# 02_PWR_IN.net
KiCad netlist of a schematic drawn in Altium Designer
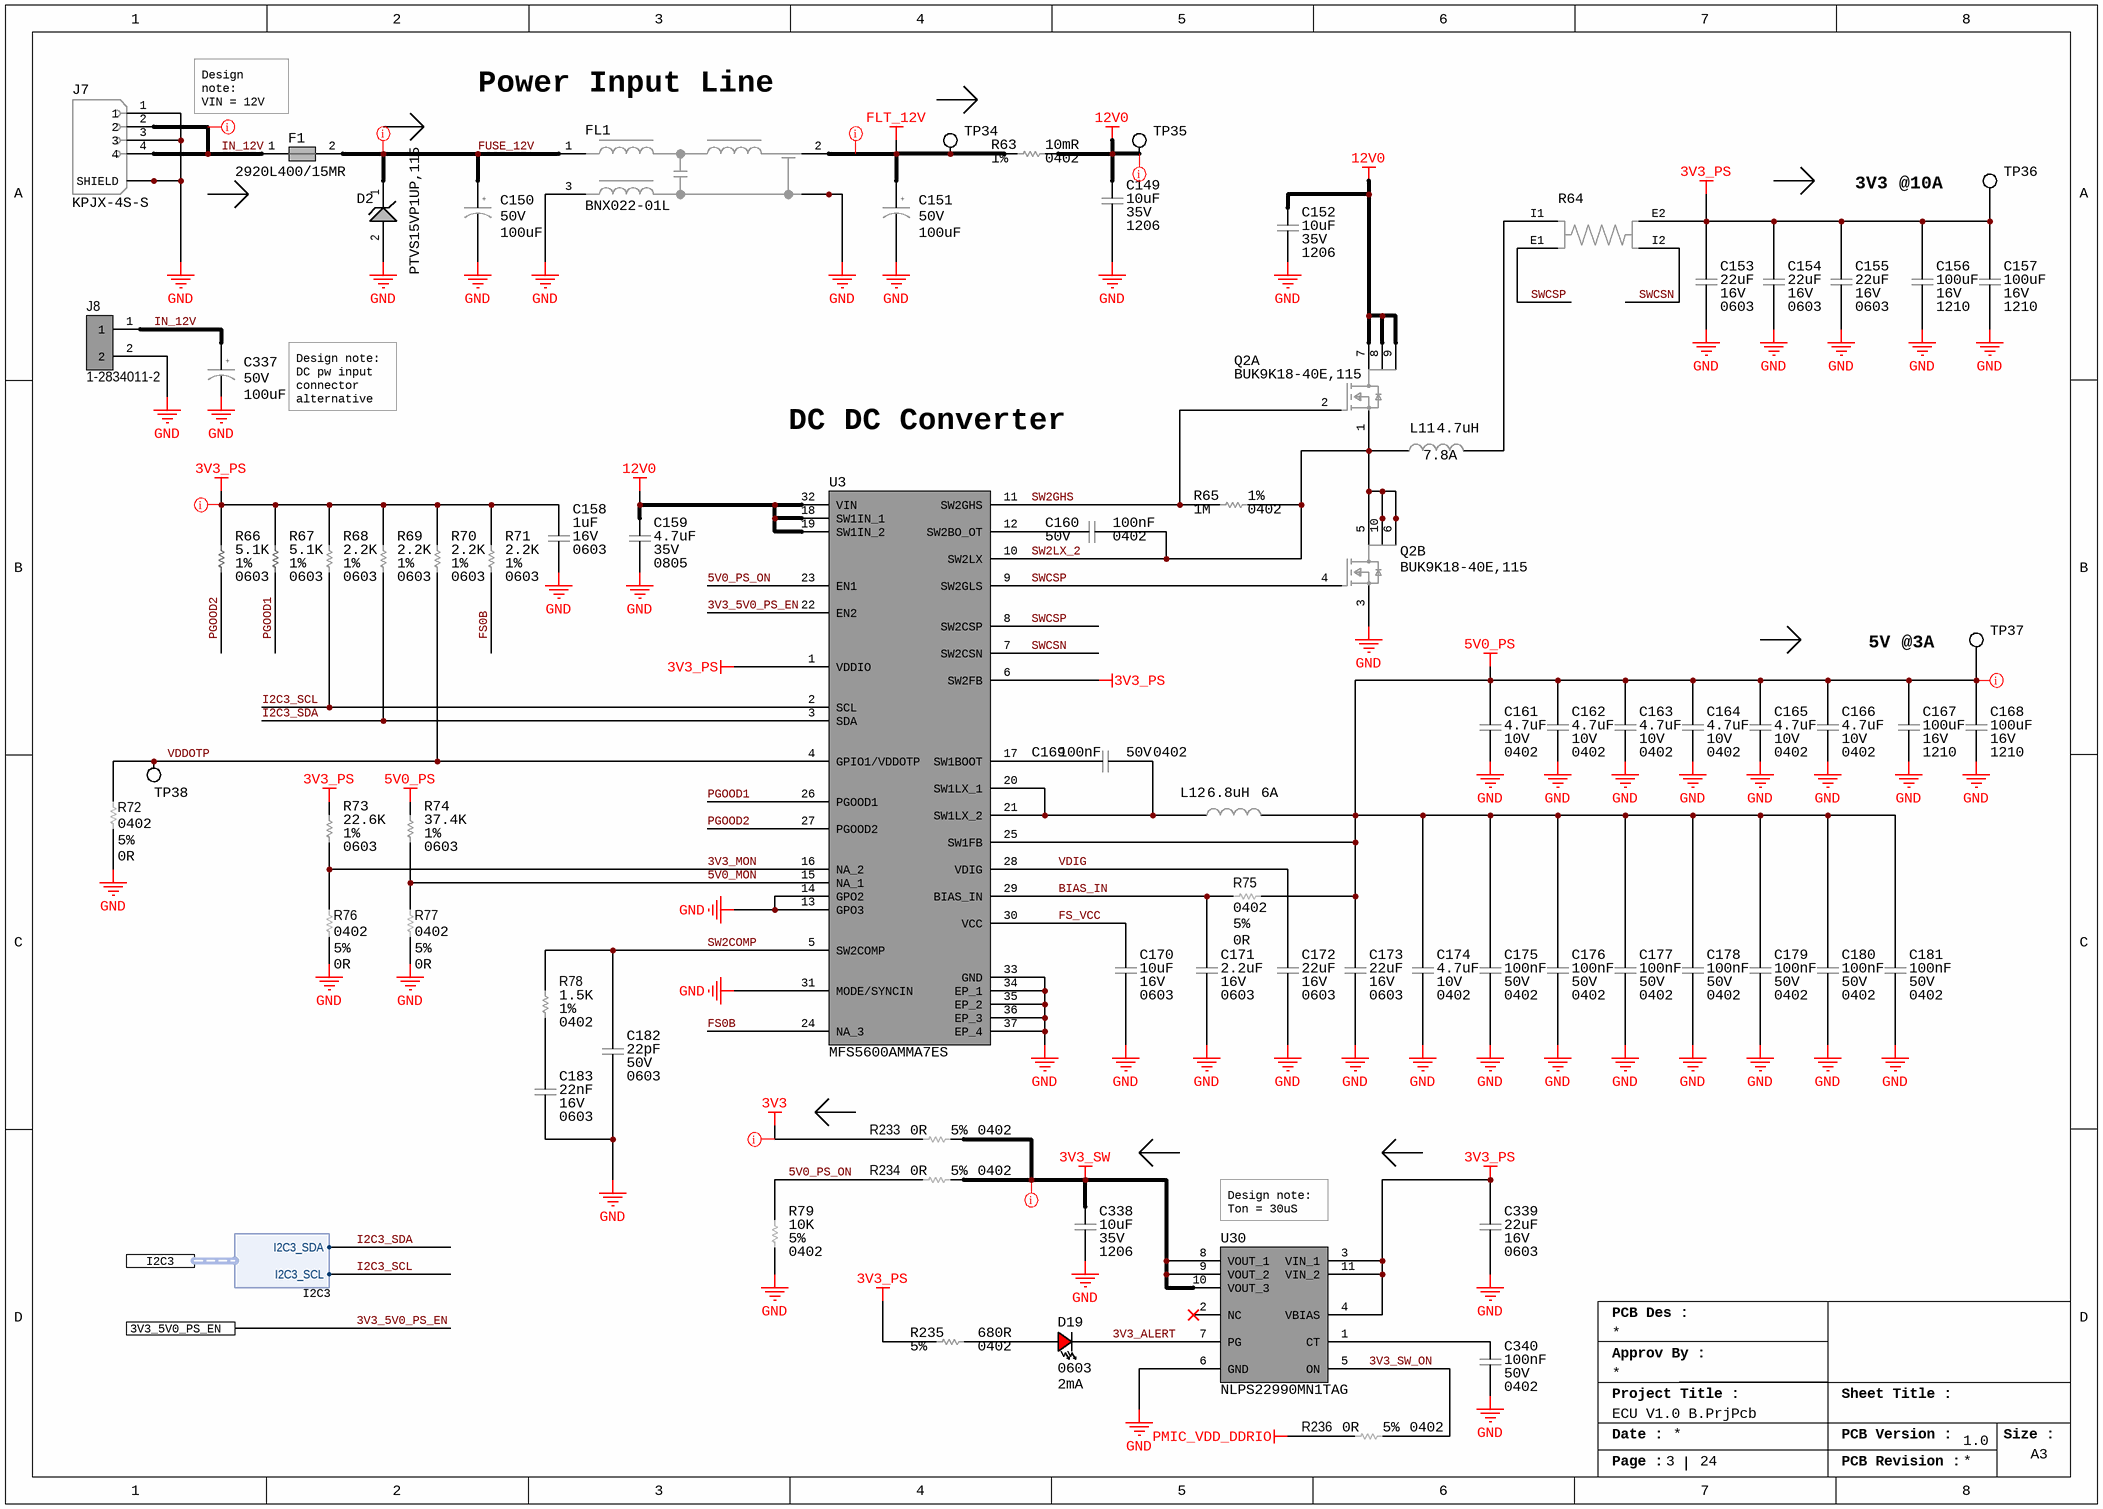
[diagram p0: 02_PWR IN.SchDoc]

(export (version "E")
  (design (tool "Eeschema 10.0.6"))
  (components
    (comp (ref "C149")
      (value "GRM319R6YA106KA12D")
      (footprint "CAP_1206_CAPC3216X16N")
      (description "1206 10 uF 35 V ±10 % Tolerance X5R SMT Multilayer Ceramic Capacitor")
      (fields
        (field (name "MANUFACTURER") "Murata")
        (field (name "TOLERANCE") "10%")
        (field (name "VOLTAGE RATING") "35V")
        (field (name "CAPACITANCE") "10uF")
        (field (name "CASE/PACKAGE") "1206")
      )
      (libsource (lib "Electronic Devices_LIB") (part "CAP_10uF_35V_X5R_1206"))
    )
    (comp (ref "C150")
      (value "UUD1H101MNL1GS")
      (footprint "CAP_POLA_UD(8X10)")
      (description "Radial Can - SMD ALUMINUM ELECTROLYTIC CAPACITOR UUD 50V 100muF ±20% 0.315Dia 8.00mm")
      (fields
        (field (name "MANUFACTURER") "Nichicon")
        (field (name "TOLERANCE") "20%")
        (field (name "VOLTAGE RATING (DC)") "50V")
        (field (name "CAPACITANCE") "100uF")
      )
      (libsource (lib "Electronic Devices_LIB") (part "CAP_100UF_50V_POL"))
    )
    (comp (ref "C151")
      (value "UUD1H101MNL1GS")
      (footprint "CAP_POLA_UD(8X10)")
      (description "Radial Can - SMD ALUMINUM ELECTROLYTIC CAPACITOR UUD 50V 100muF ±20% 0.315Dia 8.00mm")
      (fields
        (field (name "MANUFACTURER") "Nichicon")
        (field (name "TOLERANCE") "20%")
        (field (name "VOLTAGE RATING (DC)") "50V")
        (field (name "CAPACITANCE") "100uF")
      )
      (libsource (lib "Electronic Devices_LIB") (part "CAP_100UF_50V_POL"))
    )
    (comp (ref "C152")
      (value "GRM319R6YA106KA12D")
      (footprint "CAP_1206_CAPC3216X16N")
      (description "1206 10 uF 35 V ±10 % Tolerance X5R SMT Multilayer Ceramic Capacitor")
      (fields
        (field (name "MANUFACTURER") "Murata")
        (field (name "TOLERANCE") "10%")
        (field (name "VOLTAGE RATING") "35V")
        (field (name "CAPACITANCE") "10uF")
        (field (name "CASE/PACKAGE") "1206")
      )
      (libsource (lib "Electronic Devices_LIB") (part "CAP_10uF_35V_X5R_1206"))
    )
    (comp (ref "C153")
      (value "CL10A226MO7JZNC")
      (footprint "CAP_0603_CAPC1608X08N")
      (description "Cap Ceramic 22uF 16V X5R 20% Pad SMD 0603 85C T/R")
      (fields
        (field (name "MANUFACTURER") "Samsung")
        (field (name "TOLERANCE") "20%")
        (field (name "CAPACITANCE") "22uF")
        (field (name "VOLTAGE RATING") "16V")
        (field (name "CASE/PACKAGE") "0603")
      )
      (libsource (lib "Electronic Devices_LIB") (part "CAP_22UF_16V_X5R_0603"))
    )
    (comp (ref "C154")
      (value "CL10A226MO7JZNC")
      (footprint "CAP_0603_CAPC1608X08N")
      (description "Cap Ceramic 22uF 16V X5R 20% Pad SMD 0603 85C T/R")
      (fields
        (field (name "MANUFACTURER") "Samsung")
        (field (name "TOLERANCE") "20%")
        (field (name "CAPACITANCE") "22uF")
        (field (name "VOLTAGE RATING") "16V")
        (field (name "CASE/PACKAGE") "0603")
      )
      (libsource (lib "Electronic Devices_LIB") (part "CAP_22UF_16V_X5R_0603"))
    )
    (comp (ref "C155")
      (value "CL10A226MO7JZNC")
      (footprint "CAP_0603_CAPC1608X08N")
      (description "Cap Ceramic 22uF 16V X5R 20% Pad SMD 0603 85C T/R")
      (fields
        (field (name "MANUFACTURER") "Samsung")
        (field (name "TOLERANCE") "20%")
        (field (name "CAPACITANCE") "22uF")
        (field (name "VOLTAGE RATING") "16V")
        (field (name "CASE/PACKAGE") "0603")
      )
      (libsource (lib "Electronic Devices_LIB") (part "CAP_22UF_16V_X5R_0603"))
    )
    (comp (ref "C156")
      (value "EMK325ABJ107MM-T")
      (footprint "CAP_1210_CAPC3225X270N")
      (description "Multilayer Ceramic Capacitor, 100 uF, 16 V, ± 20%, X5R, 1210 [3225 Metric]")
      (fields
        (field (name "MANUFACTURER") "Taiyo Yuden")
        (field (name "TOLERANCE") "20%")
        (field (name "VOLTAGE RATING") "16V")
        (field (name "CAPACITANCE") "100uF")
        (field (name "CASE/PACKAGE") "1210")
      )
      (libsource (lib "Electronic Devices_LIB") (part "CAP_100UF_16V_X5R_1210"))
    )
    (comp (ref "C157")
      (value "EMK325ABJ107MM-T")
      (footprint "CAP_1210_CAPC3225X270N")
      (description "Multilayer Ceramic Capacitor, 100 uF, 16 V, ± 20%, X5R, 1210 [3225 Metric]")
      (fields
        (field (name "MANUFACTURER") "Taiyo Yuden")
        (field (name "TOLERANCE") "20%")
        (field (name "VOLTAGE RATING") "16V")
        (field (name "CAPACITANCE") "100uF")
        (field (name "CASE/PACKAGE") "1210")
      )
      (libsource (lib "Electronic Devices_LIB") (part "CAP_100UF_16V_X5R_1210"))
    )
    (comp (ref "C158")
      (value "CL10A105KO8NNNC")
      (footprint "CAP_0603_CAPC1608X08N")
      (description "CAP CER 1UF 16V X5R 0603")
      (fields
        (field (name "MANUFACTURER") "Samsung")
        (field (name "TOLERANCE") "10%")
        (field (name "VOLTAGE RATING") "16V")
        (field (name "CAPACITANCE") "1uF")
        (field (name "CASE/PACKAGE") "0603")
      )
      (libsource (lib "Electronic Devices_LIB") (part "CAP_1UF_16V_X5R_0603"))
    )
    (comp (ref "C159")
      (value "CL21A475KLCLQNC")
      (footprint "CAP_0805_CAPC2012X12N")
      (description "CL Series 0805 35 V 4.7 uF ±10% Tolerance X5R Multilayer Ceramic Chip Capacitor")
      (fields
        (field (name "MANUFACTURER") "Samsung")
        (field (name "TOLERANCE") "10%")
        (field (name "VOLTAGE RATING") "35V")
        (field (name "CAPACITANCE") "4.7uF")
        (field (name "CASE/PACKAGE") "0805")
      )
      (libsource (lib "Electronic Devices_LIB") (part "CAP_4.7uF_35V_X5R_0805"))
    )
    (comp (ref "C160")
      (value "GRM155R71H104KE14D")
      (footprint "CAP_0402_CAPC1005X05N")
      (description "Multilayer Ceramic Capacitor, 0.1 uF, 16 V, ± 10%, X7R, 0402 [1005 Metric]")
      (fields
        (field (name "MANUFACTURER") "Murata")
        (field (name "TOLERANCE") "10%")
        (field (name "VOLTAGE RATING") "50V")
        (field (name "CAPACITANCE") "100nF")
        (field (name "CASE/PACKAGE") "0402")
      )
      (libsource (lib "Electronic Devices_LIB") (part "CAP_100NF_50V_X7R_0402"))
    )
    (comp (ref "C161")
      (value "CL05A475KP5NRNC")
      (footprint "CAP_0402_CAPC1005X05N")
      (description "Multilayer Ceramic Capacitor, 4.7 uF, 10 V, ± 10%, X5R, 0402 [1005 Metric]")
      (fields
        (field (name "MANUFACTURER") "Samsung")
        (field (name "TOLERANCE") "10%")
        (field (name "CAPACITANCE") "4.7uF")
        (field (name "VOLTAGE RATING") "10V")
        (field (name "CASE/PACKAGE") "0402")
      )
      (libsource (lib "Electronic Devices_LIB") (part "CAP_4.7UF_10V_X5R_0402"))
    )
    (comp (ref "C162")
      (value "CL05A475KP5NRNC")
      (footprint "CAP_0402_CAPC1005X05N")
      (description "Multilayer Ceramic Capacitor, 4.7 uF, 10 V, ± 10%, X5R, 0402 [1005 Metric]")
      (fields
        (field (name "MANUFACTURER") "Samsung")
        (field (name "TOLERANCE") "10%")
        (field (name "CAPACITANCE") "4.7uF")
        (field (name "VOLTAGE RATING") "10V")
        (field (name "CASE/PACKAGE") "0402")
      )
      (libsource (lib "Electronic Devices_LIB") (part "CAP_4.7UF_10V_X5R_0402"))
    )
    (comp (ref "C163")
      (value "CL05A475KP5NRNC")
      (footprint "CAP_0402_CAPC1005X05N")
      (description "Multilayer Ceramic Capacitor, 4.7 uF, 10 V, ± 10%, X5R, 0402 [1005 Metric]")
      (fields
        (field (name "MANUFACTURER") "Samsung")
        (field (name "TOLERANCE") "10%")
        (field (name "CAPACITANCE") "4.7uF")
        (field (name "VOLTAGE RATING") "10V")
        (field (name "CASE/PACKAGE") "0402")
      )
      (libsource (lib "Electronic Devices_LIB") (part "CAP_4.7UF_10V_X5R_0402"))
    )
    (comp (ref "C164")
      (value "CL05A475KP5NRNC")
      (footprint "CAP_0402_CAPC1005X05N")
      (description "Multilayer Ceramic Capacitor, 4.7 uF, 10 V, ± 10%, X5R, 0402 [1005 Metric]")
      (fields
        (field (name "MANUFACTURER") "Samsung")
        (field (name "TOLERANCE") "10%")
        (field (name "CAPACITANCE") "4.7uF")
        (field (name "VOLTAGE RATING") "10V")
        (field (name "CASE/PACKAGE") "0402")
      )
      (libsource (lib "Electronic Devices_LIB") (part "CAP_4.7UF_10V_X5R_0402"))
    )
    (comp (ref "C165")
      (value "CL05A475KP5NRNC")
      (footprint "CAP_0402_CAPC1005X05N")
      (description "Multilayer Ceramic Capacitor, 4.7 uF, 10 V, ± 10%, X5R, 0402 [1005 Metric]")
      (fields
        (field (name "MANUFACTURER") "Samsung")
        (field (name "TOLERANCE") "10%")
        (field (name "CAPACITANCE") "4.7uF")
        (field (name "VOLTAGE RATING") "10V")
        (field (name "CASE/PACKAGE") "0402")
      )
      (libsource (lib "Electronic Devices_LIB") (part "CAP_4.7UF_10V_X5R_0402"))
    )
    (comp (ref "C166")
      (value "CL05A475KP5NRNC")
      (footprint "CAP_0402_CAPC1005X05N")
      (description "Multilayer Ceramic Capacitor, 4.7 uF, 10 V, ± 10%, X5R, 0402 [1005 Metric]")
      (fields
        (field (name "MANUFACTURER") "Samsung")
        (field (name "TOLERANCE") "10%")
        (field (name "CAPACITANCE") "4.7uF")
        (field (name "VOLTAGE RATING") "10V")
        (field (name "CASE/PACKAGE") "0402")
      )
      (libsource (lib "Electronic Devices_LIB") (part "CAP_4.7UF_10V_X5R_0402"))
    )
    (comp (ref "C167")
      (value "EMK325ABJ107MM-T")
      (footprint "CAP_1210_CAPC3225X270N")
      (description "Multilayer Ceramic Capacitor, 100 uF, 16 V, ± 20%, X5R, 1210 [3225 Metric]")
      (fields
        (field (name "MANUFACTURER") "Taiyo Yuden")
        (field (name "TOLERANCE") "20%")
        (field (name "VOLTAGE RATING") "16V")
        (field (name "CAPACITANCE") "100uF")
        (field (name "CASE/PACKAGE") "1210")
      )
      (libsource (lib "Electronic Devices_LIB") (part "CAP_100UF_16V_X5R_1210"))
    )
    (comp (ref "C168")
      (value "EMK325ABJ107MM-T")
      (footprint "CAP_1210_CAPC3225X270N")
      (description "Multilayer Ceramic Capacitor, 100 uF, 16 V, ± 20%, X5R, 1210 [3225 Metric]")
      (fields
        (field (name "MANUFACTURER") "Taiyo Yuden")
        (field (name "TOLERANCE") "20%")
        (field (name "VOLTAGE RATING") "16V")
        (field (name "CAPACITANCE") "100uF")
        (field (name "CASE/PACKAGE") "1210")
      )
      (libsource (lib "Electronic Devices_LIB") (part "CAP_100UF_16V_X5R_1210"))
    )
    (comp (ref "C169")
      (value "GRM155R71H104KE14D")
      (footprint "CAP_0402_CAPC1005X05N")
      (description "Multilayer Ceramic Capacitor, 0.1 uF, 16 V, ± 10%, X7R, 0402 [1005 Metric]")
      (fields
        (field (name "MANUFACTURER") "Murata")
        (field (name "TOLERANCE") "10%")
        (field (name "VOLTAGE RATING") "50V")
        (field (name "CAPACITANCE") "100nF")
        (field (name "CASE/PACKAGE") "0402")
      )
      (libsource (lib "Electronic Devices_LIB") (part "CAP_100NF_50V_X7R_0402"))
    )
    (comp (ref "C170")
      (value "GRM188R61C106MAALD")
      (footprint "CAP_0603_CAPC1608X08N")
      (description "0603 10 uF 16 V ±20% Tolerance X5R Multilayer Ceramic Chip Capacitor")
      (fields
        (field (name "MANUFACTURER") "Murata")
        (field (name "TOLERANCE") "20%")
        (field (name "VOLTAGE RATING") "16V")
        (field (name "CAPACITANCE") "10uF")
        (field (name "CASE/PACKAGE") "0603")
      )
      (libsource (lib "Electronic Devices_LIB") (part "CAP_10UF_16V_X5R_0603"))
    )
    (comp (ref "C171")
      (value "EMK107BB7225KA-T")
      (footprint "CAP_0603_CAPC1608X08N")
      (description "Multilayer Ceramic Capacitors (High dielectric type), 16V, 2.2 uF, ± 10 %, 0603, X7R, RoHS")
      (fields
        (field (name "MANUFACTURER") "Taiyo Yuden")
        (field (name "TOLERANCE") "10%")
        (field (name "CASE/PACKAGE") "0603")
        (field (name "CAPACITANCE") "2.2uF")
        (field (name "VOLTAGE RATING") "16V")
      )
      (libsource (lib "Electronic Devices_LIB") (part "CAP_2.2UF_16V_X7R_0603"))
    )
    (comp (ref "C172")
      (value "CL10A226MO7JZNC")
      (footprint "CAP_0603_CAPC1608X08N")
      (description "Cap Ceramic 22uF 16V X5R 20% Pad SMD 0603 85C T/R")
      (fields
        (field (name "MANUFACTURER") "Samsung")
        (field (name "TOLERANCE") "20%")
        (field (name "CAPACITANCE") "22uF")
        (field (name "VOLTAGE RATING") "16V")
        (field (name "CASE/PACKAGE") "0603")
      )
      (libsource (lib "Electronic Devices_LIB") (part "CAP_22UF_16V_X5R_0603"))
    )
    (comp (ref "C173")
      (value "CL10A226MO7JZNC")
      (footprint "CAP_0603_CAPC1608X08N")
      (description "Cap Ceramic 22uF 16V X5R 20% Pad SMD 0603 85C T/R")
      (fields
        (field (name "MANUFACTURER") "Samsung")
        (field (name "TOLERANCE") "20%")
        (field (name "CAPACITANCE") "22uF")
        (field (name "VOLTAGE RATING") "16V")
        (field (name "CASE/PACKAGE") "0603")
      )
      (libsource (lib "Electronic Devices_LIB") (part "CAP_22UF_16V_X5R_0603"))
    )
    (comp (ref "C174")
      (value "CL05A475KP5NRNC")
      (footprint "CAP_0402_CAPC1005X05N")
      (description "Multilayer Ceramic Capacitor, 4.7 uF, 10 V, ± 10%, X5R, 0402 [1005 Metric]")
      (fields
        (field (name "MANUFACTURER") "Samsung")
        (field (name "TOLERANCE") "10%")
        (field (name "CAPACITANCE") "4.7uF")
        (field (name "VOLTAGE RATING") "10V")
        (field (name "CASE/PACKAGE") "0402")
      )
      (libsource (lib "Electronic Devices_LIB") (part "CAP_4.7UF_10V_X5R_0402"))
    )
    (comp (ref "C175")
      (value "GRM155R71H104KE14D")
      (footprint "CAP_0402_CAPC1005X05N")
      (description "Multilayer Ceramic Capacitor, 0.1 uF, 16 V, ± 10%, X7R, 0402 [1005 Metric]")
      (fields
        (field (name "MANUFACTURER") "Murata")
        (field (name "TOLERANCE") "10%")
        (field (name "VOLTAGE RATING") "50V")
        (field (name "CAPACITANCE") "100nF")
        (field (name "CASE/PACKAGE") "0402")
      )
      (libsource (lib "Electronic Devices_LIB") (part "CAP_100NF_50V_X7R_0402"))
    )
    (comp (ref "C176")
      (value "GRM155R71H104KE14D")
      (footprint "CAP_0402_CAPC1005X05N")
      (description "Multilayer Ceramic Capacitor, 0.1 uF, 16 V, ± 10%, X7R, 0402 [1005 Metric]")
      (fields
        (field (name "MANUFACTURER") "Murata")
        (field (name "TOLERANCE") "10%")
        (field (name "VOLTAGE RATING") "50V")
        (field (name "CAPACITANCE") "100nF")
        (field (name "CASE/PACKAGE") "0402")
      )
      (libsource (lib "Electronic Devices_LIB") (part "CAP_100NF_50V_X7R_0402"))
    )
    (comp (ref "C177")
      (value "GRM155R71H104KE14D")
      (footprint "CAP_0402_CAPC1005X05N")
      (description "Multilayer Ceramic Capacitor, 0.1 uF, 16 V, ± 10%, X7R, 0402 [1005 Metric]")
      (fields
        (field (name "MANUFACTURER") "Murata")
        (field (name "TOLERANCE") "10%")
        (field (name "VOLTAGE RATING") "50V")
        (field (name "CAPACITANCE") "100nF")
        (field (name "CASE/PACKAGE") "0402")
      )
      (libsource (lib "Electronic Devices_LIB") (part "CAP_100NF_50V_X7R_0402"))
    )
    (comp (ref "C178")
      (value "GRM155R71H104KE14D")
      (footprint "CAP_0402_CAPC1005X05N")
      (description "Multilayer Ceramic Capacitor, 0.1 uF, 16 V, ± 10%, X7R, 0402 [1005 Metric]")
      (fields
        (field (name "MANUFACTURER") "Murata")
        (field (name "TOLERANCE") "10%")
        (field (name "VOLTAGE RATING") "50V")
        (field (name "CAPACITANCE") "100nF")
        (field (name "CASE/PACKAGE") "0402")
      )
      (libsource (lib "Electronic Devices_LIB") (part "CAP_100NF_50V_X7R_0402"))
    )
    (comp (ref "C179")
      (value "GRM155R71H104KE14D")
      (footprint "CAP_0402_CAPC1005X05N")
      (description "Multilayer Ceramic Capacitor, 0.1 uF, 16 V, ± 10%, X7R, 0402 [1005 Metric]")
      (fields
        (field (name "MANUFACTURER") "Murata")
        (field (name "TOLERANCE") "10%")
        (field (name "VOLTAGE RATING") "50V")
        (field (name "CAPACITANCE") "100nF")
        (field (name "CASE/PACKAGE") "0402")
      )
      (libsource (lib "Electronic Devices_LIB") (part "CAP_100NF_50V_X7R_0402"))
    )
    (comp (ref "C180")
      (value "GRM155R71H104KE14D")
      (footprint "CAP_0402_CAPC1005X05N")
      (description "Multilayer Ceramic Capacitor, 0.1 uF, 16 V, ± 10%, X7R, 0402 [1005 Metric]")
      (fields
        (field (name "MANUFACTURER") "Murata")
        (field (name "TOLERANCE") "10%")
        (field (name "VOLTAGE RATING") "50V")
        (field (name "CAPACITANCE") "100nF")
        (field (name "CASE/PACKAGE") "0402")
      )
      (libsource (lib "Electronic Devices_LIB") (part "CAP_100NF_50V_X7R_0402"))
    )
    (comp (ref "C181")
      (value "GRM155R71H104KE14D")
      (footprint "CAP_0402_CAPC1005X05N")
      (description "Multilayer Ceramic Capacitor, 0.1 uF, 16 V, ± 10%, X7R, 0402 [1005 Metric]")
      (fields
        (field (name "MANUFACTURER") "Murata")
        (field (name "TOLERANCE") "10%")
        (field (name "VOLTAGE RATING") "50V")
        (field (name "CAPACITANCE") "100nF")
        (field (name "CASE/PACKAGE") "0402")
      )
      (libsource (lib "Electronic Devices_LIB") (part "CAP_100NF_50V_X7R_0402"))
    )
    (comp (ref "C182")
      (value "C0603C220J5GACTU")
      (footprint "CAP_0603_CAPC1608X08N")
      (description "Multilayer Ceramic Capacitor, 22 pF, 50 V, ï¿½ 5%, C0G (NP0), 0603 [1608 Metric]")
      (fields
        (field (name "MANUFACTURER") "KEMET")
        (field (name "TOLERANCE") "5%")
        (field (name "VOLTAGE RATING (DC)") "50V")
        (field (name "CAPACITANCE") "22pF")
        (field (name "CASE/PACKAGE") "0603")
      )
      (libsource (lib "Electronic Devices_LIB") (part "CAP_22pF_50V_NP0_0603"))
    )
    (comp (ref "C183")
      (value "C0603C223K4RACTU")
      (footprint "CAP_0603_CAPC1608X08N")
      (description "Multilayer Ceramic Capacitor, 0.022 uF, 16 V, ± 10%, X7R, 0603 [1608 Metric]")
      (fields
        (field (name "MANUFACTURER") "KEMET")
        (field (name "TOLERANCE") "10%")
        (field (name "VOLTAGE RATING (DC)") "16V")
        (field (name "CAPACITANCE") "22nF")
        (field (name "CASE/PACKAGE") "0603")
      )
      (libsource (lib "Electronic Devices_LIB") (part "CAP_22nF_16V_X7R_0603"))
    )
    (comp (ref "C337")
      (value "UUD1H101MNL1GS")
      (footprint "CAP_POLA_UD(8X10)")
      (description "Radial Can - SMD ALUMINUM ELECTROLYTIC CAPACITOR UUD 50V 100muF ±20% 0.315Dia 8.00mm")
      (fields
        (field (name "MANUFACTURER") "Nichicon")
        (field (name "TOLERANCE") "20%")
        (field (name "VOLTAGE RATING (DC)") "50V")
        (field (name "CAPACITANCE") "100uF")
      )
      (libsource (lib "Electronic Devices_LIB") (part "CAP_100UF_50V_POL"))
    )
    (comp (ref "C338")
      (value "GRM319R6YA106KA12D")
      (footprint "CAP_1206_CAPC3216X16N")
      (description "1206 10 uF 35 V ±10 % Tolerance X5R SMT Multilayer Ceramic Capacitor")
      (fields
        (field (name "MANUFACTURER") "Murata")
        (field (name "TOLERANCE") "10%")
        (field (name "VOLTAGE RATING") "35V")
        (field (name "CAPACITANCE") "10uF")
        (field (name "CASE/PACKAGE") "1206")
      )
      (libsource (lib "Electronic Devices_LIB") (part "CAP_10uF_35V_X5R_1206"))
    )
    (comp (ref "C339")
      (value "CL10A226MO7JZNC")
      (footprint "CAP_0603_CAPC1608X08N")
      (description "Cap Ceramic 22uF 16V X5R 20% Pad SMD 0603 85C T/R")
      (fields
        (field (name "MANUFACTURER") "Samsung")
        (field (name "TOLERANCE") "20%")
        (field (name "CAPACITANCE") "22uF")
        (field (name "VOLTAGE RATING") "16V")
        (field (name "CASE/PACKAGE") "0603")
      )
      (libsource (lib "Electronic Devices_LIB") (part "CAP_22UF_16V_X5R_0603"))
    )
    (comp (ref "C340")
      (value "GRM155R71H104KE14D")
      (footprint "CAP_0402_CAPC1005X05N")
      (description "Multilayer Ceramic Capacitor, 0.1 uF, 16 V, ± 10%, X7R, 0402 [1005 Metric]")
      (fields
        (field (name "MANUFACTURER") "Murata")
        (field (name "TOLERANCE") "10%")
        (field (name "VOLTAGE RATING") "50V")
        (field (name "CAPACITANCE") "100nF")
        (field (name "CASE/PACKAGE") "0402")
      )
      (libsource (lib "Electronic Devices_LIB") (part "CAP_100NF_50V_X7R_0402"))
    )
    (comp (ref "D2")
      (value "PTVS15VP1UP,115")
      (footprint "PMEG3050EP115")
      (description "TVS DIODE 15VWM 24.4VC SOD128")
      (fields (field (name "MANUFACTURER") "Nexperia"))
      (libsource (lib "Electronic Devices_LIB") (part "DIO_TVS_24.4V_PTVS15VP1UP,115"))
    )
    (comp (ref "D19")
      (value "LTST-C193KRKT-2A")
      (footprint "LED_0603-RED-0.75mm")
      (description "Led Red Clear 0603 Smd")
      (fields
        (field (name "MANUFACTURER") "Vishay Lite-On")
        (field (name "CASE/PACKAGE") "0603")
        (field (name "TEST CURRENT") "2mA")
      )
      (libsource (lib "Electronic Devices_LIB") (part "LED_DIO_RED_2mA_0603_LTST-C193KRKT-2A"))
    )
    (comp (ref "F1")
      (value "2920L400/15MR")
      (footprint "2920L07560MR")
      (description "PTC Resettable Fuse 4A(hold) 8A(trip) 15VDC 40A 1.5W 4s 0.01Ohm SMD Solder Pad 2920 T/R")
      (fields (field (name "MANUFACTURER") "Littelfuse"))
      (libsource (lib "Electronic Devices_LIB") (part "FUSE_PTC_8A_2920L400/15MR"))
    )
    (comp (ref "FL1")
      (value "BNX022-01L")
      (footprint "FILTER_BNX022-01L")
      (description "EMI Filter 1MHz to 1000MHz 35dB 10A 50VDC Flat Style SMD Embossed T/R")
      (fields (field (name "MANUFACTURER") "Murata"))
      (libsource (lib "Electronic Devices_LIB") (part "FILTER_EMI_50VDC_10A_BNX022-01L"))
    )
    (comp (ref "J7")
      (value "KPJX-4S-S")
      (footprint "CONN_DC_KYCON_KPJX-4S-S")
      (description "Conn Power SKT 4 POS Solder ST Thru-Hole 4 Terminal 1 Port")
      (fields (field (name "MANUFACTURER") "Kycon"))
      (libsource (lib "Electronic Devices_LIB") (part "CONN_DC_JACK_PWR_KPJX-4S-S"))
    )
    (comp (ref "J8")
      (value "1-2834011-2")
      (footprint "CONN_TBLOCK_128340112")
      (description "2POS3.5MMTOPENTRYSCREWLESSC")
      (fields (field (name "MANUFACTURER") "TE Connectivity") (field (name "VOLTAGE") "300V"))
      (libsource (lib "Electronic Devices_LIB") (part "CONN_TBLOCK_2P_3.5mm_1-2834011-2"))
    )
    (comp (ref "L11")
      (value "SPM7054VT-4R7M-D")
      (footprint "SPM7054VT")
      (description "Inductor Power Shielded Wirewound 4.7uH 20% 100KHz Metal 7.8A 0.01826Ohm DCR Automotive T/R")
      (fields
        (field (name "MANUFACTURER") "TDK")
        (field (name "CURRENT RATING") "7.8A")
        (field (name "INDUCTANCE") "4.7uH")
      )
      (libsource (lib "Electronic Devices_LIB") (part "IND_4.7uH_7.8A_SPM7054VT-4R7M-D"))
    )
    (comp (ref "L12")
      (value "74437368068")
      (footprint "WE-LHMI_104048")
      (description "WE-LHMI; 6800 nH; Composite Iron Multilayer SMD Inductor; 1040 Case; .013GHz 6A")
      (fields
        (field (name "MANUFACTURER") "Wurth Electronics")
        (field (name "TOLERANCE") "20%")
        (field (name "MAX DC CURRENT") "6A")
        (field (name "INDUCTANCE") "6.8uH")
      )
      (libsource (lib "Electronic Devices_LIB") (part "IND_6.8uH_6A_74437368068"))
    )
    (comp (ref "Q2")
      (value "BUK9K18-40E,115")
      (footprint "BUK9K1840E115")
      (description "Transistor MOSFET Array Dual N -CH 40V 30A 8-Pin LFPAK-56D T/R")
      (fields (field (name "MANUFACTURER") "Nexperia"))
      (libsource (lib "Electronic Devices_LIB") (part "TRANS_FET_CH__N_40V_30A_BUK9K18-40E,115"))
    )
    (comp (ref "R63")
      (value "ERJ-2LWFR010X")
      (footprint "RES_0603_RESC1608X04N")
      (description "Res Current Sense Thick Film 0402 0.01 Ohm 1% 1/5W 0ppm/°C to 500ppm/°C Molded T/R")
      (fields
        (field (name "MANUFACTURER") "Panasonic")
        (field (name "TOLERANCE") "1%")
        (field (name "RESISTANCE") "10mR")
        (field (name "CASE/PACKAGE") "0402")
      )
      (libsource (lib "Electronic Devices_LIB") (part "RES_10mR_1%_0.05W_0402"))
    )
    (comp (ref "R64")
      (value "WSK2512R0100FEA")
      (footprint "RES_WSK2512R0100FEA")
      (description "Fixed Resistor, Metal Strip, 1W, 0.01ohm, 0.1V, 1% +/-Tol, 35ppm/Cel, Surface Mount, 2512")
      (fields (field (name "MANUFACTURER") "Vishay") (field (name "TOLERANCE") "1%"))
      (libsource (lib "Electronic Devices_LIB") (part "RES_10mR_1%_1W_2512"))
    )
    (comp (ref "R65")
      (value "CR0402-FX-1004GLF")
      (footprint "RES_0402_RESC1005X04N")
      (description "Res Thick Film 0402 1M Ohm 1% 1/16W ±100ppm/°C Molded SMD SMD Paper Tape on Plastic Reel")
      (fields
        (field (name "MANUFACTURER") "Bourns")
        (field (name "RESISTANCE") "1M")
        (field (name "TOLERANCE") "1%")
        (field (name "CASE/PACKAGE") "0402")
      )
      (libsource (lib "Electronic Devices_LIB") (part "RES_1M_1%_63mW_0402"))
    )
    (comp (ref "R66")
      (value "RC0603FR-075K1L")
      (footprint "RES_0603_RESC1608X04N")
      (description "SMD Chip Resistor, 5.1 kOhm, ± 1%, 100 mW, 0603 [1608 Metric], Thick Film, General Purpose")
      (fields
        (field (name "MANUFACTURER") "Yageo")
        (field (name "TOLERANCE") "1%")
        (field (name "RESISTANCE") "5.1K")
        (field (name "CASE/PACKAGE") "0603")
      )
      (libsource (lib "Electronic Devices_LIB") (part "RES_5.1K_1%_100mW_0603"))
    )
    (comp (ref "R67")
      (value "RC0603FR-075K1L")
      (footprint "RES_0603_RESC1608X04N")
      (description "SMD Chip Resistor, 5.1 kOhm, ± 1%, 100 mW, 0603 [1608 Metric], Thick Film, General Purpose")
      (fields
        (field (name "MANUFACTURER") "Yageo")
        (field (name "TOLERANCE") "1%")
        (field (name "RESISTANCE") "5.1K")
        (field (name "CASE/PACKAGE") "0603")
      )
      (libsource (lib "Electronic Devices_LIB") (part "RES_5.1K_1%_100mW_0603"))
    )
    (comp (ref "R68")
      (value "RC0603FR-072K2L")
      (footprint "RES_0603_RESC1608X04N")
      (description "SMD Chip Resistor, 2.2 Kohm, ½ 1%, 100 Mw, 0603 [1608 Metric], Thick Film, General Purpose")
      (fields
        (field (name "MANUFACTURER") "Yageo")
        (field (name "TOLERANCE") "1%")
        (field (name "RESISTANCE") "2.2K")
        (field (name "CASE/PACKAGE") "0603")
      )
      (libsource (lib "Electronic Devices_LIB") (part "RES_2.2K_1%_100mW_0603"))
    )
    (comp (ref "R69")
      (value "RC0603FR-072K2L")
      (footprint "RES_0603_RESC1608X04N")
      (description "SMD Chip Resistor, 2.2 Kohm, ½ 1%, 100 Mw, 0603 [1608 Metric], Thick Film, General Purpose")
      (fields
        (field (name "MANUFACTURER") "Yageo")
        (field (name "TOLERANCE") "1%")
        (field (name "RESISTANCE") "2.2K")
        (field (name "CASE/PACKAGE") "0603")
      )
      (libsource (lib "Electronic Devices_LIB") (part "RES_2.2K_1%_100mW_0603"))
    )
    (comp (ref "R70")
      (value "RC0603FR-072K2L")
      (footprint "RES_0603_RESC1608X04N")
      (description "SMD Chip Resistor, 2.2 Kohm, ½ 1%, 100 Mw, 0603 [1608 Metric], Thick Film, General Purpose")
      (fields
        (field (name "MANUFACTURER") "Yageo")
        (field (name "TOLERANCE") "1%")
        (field (name "RESISTANCE") "2.2K")
        (field (name "CASE/PACKAGE") "0603")
      )
      (libsource (lib "Electronic Devices_LIB") (part "RES_2.2K_1%_100mW_0603"))
    )
    (comp (ref "R71")
      (value "RC0603FR-072K2L")
      (footprint "RES_0603_RESC1608X04N")
      (description "SMD Chip Resistor, 2.2 Kohm, ½ 1%, 100 Mw, 0603 [1608 Metric], Thick Film, General Purpose")
      (fields
        (field (name "MANUFACTURER") "Yageo")
        (field (name "TOLERANCE") "1%")
        (field (name "RESISTANCE") "2.2K")
        (field (name "CASE/PACKAGE") "0603")
      )
      (libsource (lib "Electronic Devices_LIB") (part "RES_2.2K_1%_100mW_0603"))
    )
    (comp (ref "R72")
      (value "ERJ-2GE0R00X")
      (footprint "RES_0402_RESC1005X04N")
      (description "SMD Chip Resistor, Jumper, 0 ohm, 100 mW, 0402 [1005 Metric], Thick Film, General Purpose")
      (fields
        (field (name "MANUFACTURER") "Panasonic")
        (field (name "CASE CODE (IMPERIAL)") "0402")
        (field (name "TOLERANCE") "5%")
        (field (name "RESISTANCE") "0R")
      )
      (libsource (lib "Electronic Devices_LIB") (part "RES_0R_5%_100mW_0402"))
    )
    (comp (ref "R73")
      (value "AC0603FR-0722K6L")
      (footprint "RES_0603_RESC1608X04N")
      (description "Res Thick Film 0603 22.6K Ohm 1% 0.1W(1/10W) ±100ppm/C Pad SMD Automotive T/R")
      (fields
        (field (name "MANUFACTURER") "Yageo")
        (field (name "TOLERANCE") "1%")
        (field (name "RESISTANCE") "22.6K")
        (field (name "CASE/PACKAGE") "0603")
      )
      (libsource (lib "Electronic Devices_LIB") (part "RES_22.6K_1%_100mW_0603"))
    )
    (comp (ref "R74")
      (value "RC0603FR-0737K4L")
      (footprint "RES_0603_RESC1608X04N")
      (description "SMD Chip Resistor, 37.4 kOhm, ± 1%, 100 mW, 0603 [1608 Metric], Thick Film, General Purpose")
      (fields
        (field (name "MANUFACTURER") "Yageo")
        (field (name "TOLERANCE") "1%")
        (field (name "RESISTANCE") "37.4K")
        (field (name "CASE/PACKAGE") "0603")
      )
      (libsource (lib "Electronic Devices_LIB") (part "RES_37.4K_1%_100mW_0603"))
    )
    (comp (ref "R75")
      (value "ERJ-2GE0R00X")
      (footprint "RES_0402_RESC1005X04N")
      (description "SMD Chip Resistor, Jumper, 0 ohm, 100 mW, 0402 [1005 Metric], Thick Film, General Purpose")
      (fields
        (field (name "MANUFACTURER") "Panasonic")
        (field (name "CASE CODE (IMPERIAL)") "0402")
        (field (name "TOLERANCE") "5%")
        (field (name "RESISTANCE") "0R")
      )
      (libsource (lib "Electronic Devices_LIB") (part "RES_0R_5%_100mW_0402"))
    )
    (comp (ref "R76")
      (value "ERJ-2GE0R00X")
      (footprint "RES_0402_RESC1005X04N")
      (description "SMD Chip Resistor, Jumper, 0 ohm, 100 mW, 0402 [1005 Metric], Thick Film, General Purpose")
      (fields
        (field (name "MANUFACTURER") "Panasonic")
        (field (name "CASE CODE (IMPERIAL)") "0402")
        (field (name "TOLERANCE") "5%")
        (field (name "RESISTANCE") "0R")
      )
      (libsource (lib "Electronic Devices_LIB") (part "RES_0R_5%_100mW_0402"))
    )
    (comp (ref "R77")
      (value "ERJ-2GE0R00X")
      (footprint "RES_0402_RESC1005X04N")
      (description "SMD Chip Resistor, Jumper, 0 ohm, 100 mW, 0402 [1005 Metric], Thick Film, General Purpose")
      (fields
        (field (name "MANUFACTURER") "Panasonic")
        (field (name "CASE CODE (IMPERIAL)") "0402")
        (field (name "TOLERANCE") "5%")
        (field (name "RESISTANCE") "0R")
      )
      (libsource (lib "Electronic Devices_LIB") (part "RES_0R_5%_100mW_0402"))
    )
    (comp (ref "R78")
      (value "CR0402-FX-1501GLF")
      (footprint "RES_0402_RESC1005X04N")
      (description "Res Thick Film 0402 1.5K Ohm 1% 1/16W ±100ppm/°C Molded SMD SMD Paper Tape on Plastic Reel")
      (fields
        (field (name "MANUFACTURER") "Bourns")
        (field (name "RESISTANCE") "1.5K")
        (field (name "TOLERANCE") "1%")
        (field (name "CASE/PACKAGE") "0402")
      )
      (libsource (lib "Electronic Devices_LIB") (part "RES_1.5K_1%_63mW_0402"))
    )
    (comp (ref "R79")
      (value "ERJ-2GEJ103X")
      (footprint "RES_0402_RESC1005X04N")
      (description "Res Thick Film 0402 10K Ohm 5% 1/10W ±200ppm/°C Molded SMD Punched Carrier T/R")
      (fields
        (field (name "MANUFACTURER") "Panasonic")
        (field (name "TOLERANCE") "5%")
        (field (name "RESISTANCE") "10K")
        (field (name "CASE/PACKAGE") "0402")
      )
      (libsource (lib "Electronic Devices_LIB") (part "RES_10K_5%_100mW_0402"))
    )
    (comp (ref "R233")
      (value "ERJ-2GE0R00X")
      (footprint "RES_0402_RESC1005X04N")
      (description "SMD Chip Resistor, Jumper, 0 ohm, 100 mW, 0402 [1005 Metric], Thick Film, General Purpose")
      (fields
        (field (name "MANUFACTURER") "Panasonic")
        (field (name "CASE CODE (IMPERIAL)") "0402")
        (field (name "TOLERANCE") "5%")
        (field (name "RESISTANCE") "0R")
      )
      (libsource (lib "Electronic Devices_LIB") (part "RES_0R_5%_100mW_0402"))
    )
    (comp (ref "R234")
      (value "ERJ-2GE0R00X")
      (footprint "RES_0402_RESC1005X04N")
      (description "SMD Chip Resistor, Jumper, 0 ohm, 100 mW, 0402 [1005 Metric], Thick Film, General Purpose")
      (fields
        (field (name "MANUFACTURER") "Panasonic")
        (field (name "CASE CODE (IMPERIAL)") "0402")
        (field (name "TOLERANCE") "5%")
        (field (name "RESISTANCE") "0R")
      )
      (libsource (lib "Electronic Devices_LIB") (part "RES_0R_5%_100mW_0402"))
    )
    (comp (ref "R235")
      (value "ERJ-2GEJ681X")
      (footprint "RES_0402_RESC1005X04N")
      (description "SMD Chip Resistor, 680 Ohm, ± 5%, 100 mW, 0402 [1005 Metric], Thick Film, General Purpose")
      (fields
        (field (name "MANUFACTURER") "Panasonic")
        (field (name "TOLERANCE") "5%")
        (field (name "RESISTANCE") "680R")
        (field (name "CASE/PACKAGE") "0402")
      )
      (libsource (lib "Electronic Devices_LIB") (part "RES_680R_5%_100mW_0402"))
    )
    (comp (ref "R236")
      (value "ERJ-2GE0R00X")
      (footprint "RES_0402_RESC1005X04N")
      (description "SMD Chip Resistor, Jumper, 0 ohm, 100 mW, 0402 [1005 Metric], Thick Film, General Purpose")
      (fields
        (field (name "MANUFACTURER") "Panasonic")
        (field (name "CASE CODE (IMPERIAL)") "0402")
        (field (name "TOLERANCE") "5%")
        (field (name "RESISTANCE") "0R")
      )
      (libsource (lib "Electronic Devices_LIB") (part "RES_0R_5%_100mW_0402"))
    )
    (comp (ref "TP34")
      (value "NO COMPONENT")
      (footprint "TP_PAD_0.5MM_SMD_ROUND")
      (description "Test Point, SMD pad, round, 1.5mm, 1.6mm, 3mm diameter")
      (libsource (lib "Electronic Devices_LIB") (part "TP_PAD_SMD_SMALL"))
    )
    (comp (ref "TP35")
      (value "NO COMPONENT")
      (footprint "TP_PAD_0.5MM_SMD_ROUND")
      (description "Test Point, SMD pad, round, 1.5mm, 1.6mm, 3mm diameter")
      (libsource (lib "Electronic Devices_LIB") (part "TP_PAD_SMD_SMALL"))
    )
    (comp (ref "TP36")
      (value "NO COMPONENT")
      (footprint "TP_PAD_0.5MM_SMD_ROUND")
      (description "Test Point, SMD pad, round, 1.5mm, 1.6mm, 3mm diameter")
      (libsource (lib "Electronic Devices_LIB") (part "TP_PAD_SMD_SMALL"))
    )
    (comp (ref "TP37")
      (value "NO COMPONENT")
      (footprint "TP_PAD_0.5MM_SMD_ROUND")
      (description "Test Point, SMD pad, round, 1.5mm, 1.6mm, 3mm diameter")
      (libsource (lib "Electronic Devices_LIB") (part "TP_PAD_SMD_SMALL"))
    )
    (comp (ref "TP38")
      (value "NO COMPONENT")
      (footprint "TP_PAD_0.5MM_SMD_ROUND")
      (description "Test Point, SMD pad, round, 1.5mm, 1.6mm, 3mm diameter")
      (libsource (lib "Electronic Devices_LIB") (part "TP_PAD_SMD_SMALL"))
    )
    (comp (ref "U3")
      (value "MFS5600AMMA7ES")
      (footprint "MFS5600AMMA7ES")
      (description "Power Management, 36 V, 2 Step-Down DC-DC Converters, 2 Regulated Outputs, 32 Pins, HVQFN-EP")
      (fields (field (name "MANUFACTURER") "NXP Semiconductors"))
      (libsource (lib "Electronic Devices_LIB") (part "IC_REG_BUCK_MFS5600AMMA7ES"))
    )
    (comp (ref "U30")
      (value "NLPS22990MN1TAG")
      (footprint "SON50P200X300X80-11N")
      (description "5.5 V, 10 A, 3.9 mΩ On-Resistance Load Switch 5.5 V, 10 A, 3.9 mOhm On-Resistance")
      (fields (field (name "MANUFACTURER") "onsemi"))
      (libsource (lib "Electronic Devices_LIB") (part "IC_LOAD_SW_NLPS22990MN1TAG"))
    )
  )
  (nets
    (net (code "2") (name "/3V3_5V0_PS_EN") (class "Default")
      (node (ref "U3") (pin "22") (pinfunction "EN2_22") (pintype "passive"))
    )
    (net (code "3") (name "/3V3_ALERT") (class "Default")
      (node (ref "D19") (pin "1") (pinfunction "C_1") (pintype "passive"))
      (node (ref "U30") (pin "7") (pinfunction "PG_7") (pintype "passive"))
    )
    (net (code "4") (name "/3V3_MON") (class "Default")
      (node (ref "R73") (pin "1") (pinfunction "1_1") (pintype "passive"))
      (node (ref "R76") (pin "2") (pinfunction "2_2") (pintype "passive"))
      (node (ref "U3") (pin "16") (pinfunction "NA_2_16") (pintype "passive"))
    )
    (net (code "5") (name "/3V3_SW_ON") (class "Default")
      (node (ref "R236") (pin "1") (pinfunction "1_1") (pintype "passive"))
      (node (ref "U30") (pin "5") (pinfunction "ON_5") (pintype "passive"))
    )
    (net (code "6") (name "/5V0_MON") (class "Default")
      (node (ref "R74") (pin "1") (pinfunction "1_1") (pintype "passive"))
      (node (ref "R77") (pin "2") (pinfunction "2_2") (pintype "passive"))
      (node (ref "U3") (pin "15") (pinfunction "NA_1_15") (pintype "passive"))
    )
    (net (code "7") (name "/5V0_PS_ON") (class "Default")
      (node (ref "R234") (pin "2") (pinfunction "2_2") (pintype "passive"))
      (node (ref "R79") (pin "1") (pinfunction "1_1") (pintype "passive"))
      (node (ref "U3") (pin "23") (pinfunction "EN1_23") (pintype "passive"))
    )
    (net (code "8") (name "/BIAS_IN") (class "Default")
      (node (ref "C171") (pin "2") (pinfunction "2_2") (pintype "passive"))
      (node (ref "R75") (pin "2") (pinfunction "2_2") (pintype "passive"))
      (node (ref "U3") (pin "29") (pinfunction "BIAS_IN_29") (pintype "passive"))
    )
    (net (code "9") (name "/FS0B") (class "Default")
      (node (ref "R71") (pin "1") (pinfunction "1_1") (pintype "passive"))
      (node (ref "U3") (pin "24") (pinfunction "NA_3_24") (pintype "passive"))
    )
    (net (code "10") (name "/FS_VCC") (class "Default")
      (node (ref "C170") (pin "2") (pinfunction "2_2") (pintype "passive"))
      (node (ref "U3") (pin "30") (pinfunction "VCC_30") (pintype "passive"))
    )
    (net (code "11") (name "/FUSE_12V") (class "Default")
      (node (ref "C150") (pin "1") (pinfunction "1_1") (pintype "passive"))
      (node (ref "D2") (pin "1") (pinfunction "K_1") (pintype "passive"))
      (node (ref "F1") (pin "2") (pinfunction "2_2") (pintype "passive"))
      (node (ref "FL1") (pin "1") (pinfunction "B_1") (pintype "passive"))
    )
    (net (code "12") (name "/I2C3_SCL") (class "Default")
      (node (ref "R68") (pin "1") (pinfunction "1_1") (pintype "passive"))
      (node (ref "U3") (pin "2") (pinfunction "SCL_2") (pintype "passive"))
    )
    (net (code "13") (name "/I2C3_SDA") (class "Default")
      (node (ref "R69") (pin "1") (pinfunction "1_1") (pintype "passive"))
      (node (ref "U3") (pin "3") (pinfunction "SDA_3") (pintype "passive"))
    )
    (net (code "14") (name "/IN_12V") (class "Default")
      (node (ref "C337") (pin "1") (pinfunction "1_1") (pintype "passive"))
      (node (ref "F1") (pin "1") (pinfunction "1_1") (pintype "passive"))
      (node (ref "J7") (pin "2") (pinfunction "2_2") (pintype "passive"))
      (node (ref "J7") (pin "4") (pinfunction "4_4") (pintype "passive"))
      (node (ref "J8") (pin "1") (pinfunction "1_1") (pintype "passive"))
    )
    (net (code "15") (name "/PGOOD1") (class "Default")
      (node (ref "R67") (pin "1") (pinfunction "1_1") (pintype "passive"))
      (node (ref "U3") (pin "26") (pinfunction "PGOOD1_26") (pintype "passive"))
    )
    (net (code "16") (name "/PGOOD2") (class "Default")
      (node (ref "R66") (pin "1") (pinfunction "1_1") (pintype "passive"))
      (node (ref "U3") (pin "27") (pinfunction "PGOOD2_27") (pintype "passive"))
    )
    (net (code "17") (name "/SW2COMP") (class "Default")
      (node (ref "C182") (pin "2") (pinfunction "2_2") (pintype "passive"))
      (node (ref "R78") (pin "2") (pinfunction "2_2") (pintype "passive"))
      (node (ref "U3") (pin "5") (pinfunction "SW2COMP_5") (pintype "passive"))
    )
    (net (code "18") (name "/SW2GHS") (class "Default")
      (node (ref "Q2") (pin "2") (pinfunction "G1_2") (pintype "passive"))
      (node (ref "R65") (pin "1") (pinfunction "1_1") (pintype "passive"))
      (node (ref "U3") (pin "11") (pinfunction "SW2GHS_11") (pintype "passive"))
    )
    (net (code "19") (name "/SW2LX_2") (class "Default")
      (node (ref "C160") (pin "1") (pinfunction "1_1") (pintype "passive"))
      (node (ref "L11") (pin "1") (pinfunction "1_1") (pintype "passive"))
      (node (ref "Q2") (pin "1") (pinfunction "S1_1") (pintype "passive"))
      (node (ref "Q2") (pin "10") (pinfunction "D2_3_10") (pintype "passive"))
      (node (ref "Q2") (pin "5") (pinfunction "D2_1_5") (pintype "passive"))
      (node (ref "Q2") (pin "6") (pinfunction "D2_2_6") (pintype "passive"))
      (node (ref "R65") (pin "2") (pinfunction "2_2") (pintype "passive"))
      (node (ref "U3") (pin "10") (pinfunction "SW2LX_10") (pintype "passive"))
    )
    (net (code "20") (name "/SWCSN") (class "Default")
      (node (ref "R64") (pin "I2") (pinfunction "I2_I2") (pintype "passive"))
      (node (ref "U3") (pin "7") (pinfunction "SW2CSN_7") (pintype "passive"))
    )
    (net (code "21") (name "/SWCSP") (class "Default")
      (node (ref "Q2") (pin "4") (pinfunction "G2_4") (pintype "passive"))
      (node (ref "R64") (pin "E1") (pinfunction "E1_E1") (pintype "passive"))
      (node (ref "U3") (pin "8") (pinfunction "SW2CSP_8") (pintype "passive"))
      (node (ref "U3") (pin "9") (pinfunction "SW2GLS_9") (pintype "passive"))
    )
    (net (code "22") (name "/VDDOTP") (class "Default")
      (node (ref "R70") (pin "1") (pinfunction "1_1") (pintype "passive"))
      (node (ref "R72") (pin "2") (pinfunction "2_2") (pintype "passive"))
      (node (ref "TP38") (pin "1") (pinfunction "1_1") (pintype "passive"))
      (node (ref "U3") (pin "4") (pinfunction "GPIO1/VDDOTP_4") (pintype "passive"))
    )
    (net (code "23") (name "/VDIG") (class "Default")
      (node (ref "C172") (pin "2") (pinfunction "2_2") (pintype "passive"))
      (node (ref "U3") (pin "28") (pinfunction "VDIG_28") (pintype "passive"))
    )
    (net (code "25") (name "3V3") (class "Default")
      (node (ref "R233") (pin "2") (pinfunction "2_2") (pintype "passive"))
    )
    (net (code "26") (name "3V3_PS") (class "Default")
      (node (ref "C153") (pin "2") (pinfunction "2_2") (pintype "passive"))
      (node (ref "C154") (pin "2") (pinfunction "2_2") (pintype "passive"))
      (node (ref "C155") (pin "2") (pinfunction "2_2") (pintype "passive"))
      (node (ref "C156") (pin "2") (pinfunction "2_2") (pintype "passive"))
      (node (ref "C157") (pin "2") (pinfunction "2_2") (pintype "passive"))
      (node (ref "C158") (pin "2") (pinfunction "2_2") (pintype "passive"))
      (node (ref "C339") (pin "2") (pinfunction "2_2") (pintype "passive"))
      (node (ref "R235") (pin "1") (pinfunction "1_1") (pintype "passive"))
      (node (ref "R64") (pin "E2") (pinfunction "E2_E2") (pintype "passive"))
      (node (ref "R66") (pin "2") (pinfunction "2_2") (pintype "passive"))
      (node (ref "R67") (pin "2") (pinfunction "2_2") (pintype "passive"))
      (node (ref "R68") (pin "2") (pinfunction "2_2") (pintype "passive"))
      (node (ref "R69") (pin "2") (pinfunction "2_2") (pintype "passive"))
      (node (ref "R70") (pin "2") (pinfunction "2_2") (pintype "passive"))
      (node (ref "R71") (pin "2") (pinfunction "2_2") (pintype "passive"))
      (node (ref "R73") (pin "2") (pinfunction "2_2") (pintype "passive"))
      (node (ref "TP36") (pin "1") (pinfunction "1_1") (pintype "passive"))
      (node (ref "U3") (pin "1") (pinfunction "VDDIO_1") (pintype "passive"))
      (node (ref "U3") (pin "6") (pinfunction "SW2FB_6") (pintype "passive"))
      (node (ref "U30") (pin "11") (pinfunction "VIN_2_11") (pintype "passive"))
      (node (ref "U30") (pin "3") (pinfunction "VIN_1_3") (pintype "passive"))
      (node (ref "U30") (pin "4") (pinfunction "VBIAS_4") (pintype "passive"))
    )
    (net (code "27") (name "3V3_SW") (class "Default")
      (node (ref "C338") (pin "2") (pinfunction "2_2") (pintype "passive"))
      (node (ref "R233") (pin "1") (pinfunction "1_1") (pintype "passive"))
      (node (ref "R234") (pin "1") (pinfunction "1_1") (pintype "passive"))
      (node (ref "U30") (pin "10") (pinfunction "VOUT_3_10") (pintype "passive"))
      (node (ref "U30") (pin "8") (pinfunction "VOUT_1_8") (pintype "passive"))
      (node (ref "U30") (pin "9") (pinfunction "VOUT_2_9") (pintype "passive"))
    )
    (net (code "28") (name "5V0_PS") (class "Default")
      (node (ref "C161") (pin "2") (pinfunction "2_2") (pintype "passive"))
      (node (ref "C162") (pin "2") (pinfunction "2_2") (pintype "passive"))
      (node (ref "C163") (pin "2") (pinfunction "2_2") (pintype "passive"))
      (node (ref "C164") (pin "2") (pinfunction "2_2") (pintype "passive"))
      (node (ref "C165") (pin "2") (pinfunction "2_2") (pintype "passive"))
      (node (ref "C166") (pin "2") (pinfunction "2_2") (pintype "passive"))
      (node (ref "C167") (pin "2") (pinfunction "2_2") (pintype "passive"))
      (node (ref "C168") (pin "2") (pinfunction "2_2") (pintype "passive"))
      (node (ref "C173") (pin "2") (pinfunction "2_2") (pintype "passive"))
      (node (ref "C174") (pin "2") (pinfunction "2_2") (pintype "passive"))
      (node (ref "C175") (pin "2") (pinfunction "2_2") (pintype "passive"))
      (node (ref "C176") (pin "2") (pinfunction "2_2") (pintype "passive"))
      (node (ref "C177") (pin "2") (pinfunction "2_2") (pintype "passive"))
      (node (ref "C178") (pin "2") (pinfunction "2_2") (pintype "passive"))
      (node (ref "C179") (pin "2") (pinfunction "2_2") (pintype "passive"))
      (node (ref "C180") (pin "2") (pinfunction "2_2") (pintype "passive"))
      (node (ref "C181") (pin "2") (pinfunction "2_2") (pintype "passive"))
      (node (ref "L12") (pin "2") (pinfunction "2_2") (pintype "passive"))
      (node (ref "R74") (pin "2") (pinfunction "2_2") (pintype "passive"))
      (node (ref "R75") (pin "1") (pinfunction "1_1") (pintype "passive"))
      (node (ref "TP37") (pin "1") (pinfunction "1_1") (pintype "passive"))
      (node (ref "U3") (pin "25") (pinfunction "SW1FB_25") (pintype "passive"))
    )
    (net (code "29") (name "12V0") (class "Default")
      (node (ref "C149") (pin "2") (pinfunction "2_2") (pintype "passive"))
      (node (ref "C152") (pin "2") (pinfunction "2_2") (pintype "passive"))
      (node (ref "C159") (pin "2") (pinfunction "2_2") (pintype "passive"))
      (node (ref "Q2") (pin "7") (pinfunction "D1_1_7") (pintype "passive"))
      (node (ref "Q2") (pin "8") (pinfunction "D1_2_8") (pintype "passive"))
      (node (ref "Q2") (pin "9") (pinfunction "D1_3_9") (pintype "passive"))
      (node (ref "R63") (pin "2") (pinfunction "2_2") (pintype "passive"))
      (node (ref "TP35") (pin "1") (pinfunction "1_1") (pintype "passive"))
      (node (ref "U3") (pin "18") (pinfunction "SW1IN_1_18") (pintype "passive"))
      (node (ref "U3") (pin "19") (pinfunction "SW1IN_2_19") (pintype "passive"))
      (node (ref "U3") (pin "32") (pinfunction "VIN_32") (pintype "passive"))
    )
    (net (code "30") (name "FLT_12V") (class "Default")
      (node (ref "C151") (pin "1") (pinfunction "1_1") (pintype "passive"))
      (node (ref "FL1") (pin "2") (pinfunction "CB_2") (pintype "passive"))
      (node (ref "R63") (pin "1") (pinfunction "1_1") (pintype "passive"))
      (node (ref "TP34") (pin "1") (pinfunction "1_1") (pintype "passive"))
    )
    (net (code "31") (name "GND") (class "Default")
      (node (ref "C149") (pin "1") (pinfunction "1_1") (pintype "passive"))
      (node (ref "C150") (pin "2") (pinfunction "2_2") (pintype "passive"))
      (node (ref "C151") (pin "2") (pinfunction "2_2") (pintype "passive"))
      (node (ref "C152") (pin "1") (pinfunction "1_1") (pintype "passive"))
      (node (ref "C153") (pin "1") (pinfunction "1_1") (pintype "passive"))
      (node (ref "C154") (pin "1") (pinfunction "1_1") (pintype "passive"))
      (node (ref "C155") (pin "1") (pinfunction "1_1") (pintype "passive"))
      (node (ref "C156") (pin "1") (pinfunction "1_1") (pintype "passive"))
      (node (ref "C157") (pin "1") (pinfunction "1_1") (pintype "passive"))
      (node (ref "C158") (pin "1") (pinfunction "1_1") (pintype "passive"))
      (node (ref "C159") (pin "1") (pinfunction "1_1") (pintype "passive"))
      (node (ref "C161") (pin "1") (pinfunction "1_1") (pintype "passive"))
      (node (ref "C162") (pin "1") (pinfunction "1_1") (pintype "passive"))
      (node (ref "C163") (pin "1") (pinfunction "1_1") (pintype "passive"))
      (node (ref "C164") (pin "1") (pinfunction "1_1") (pintype "passive"))
      (node (ref "C165") (pin "1") (pinfunction "1_1") (pintype "passive"))
      (node (ref "C166") (pin "1") (pinfunction "1_1") (pintype "passive"))
      (node (ref "C167") (pin "1") (pinfunction "1_1") (pintype "passive"))
      (node (ref "C168") (pin "1") (pinfunction "1_1") (pintype "passive"))
      (node (ref "C170") (pin "1") (pinfunction "1_1") (pintype "passive"))
      (node (ref "C171") (pin "1") (pinfunction "1_1") (pintype "passive"))
      (node (ref "C172") (pin "1") (pinfunction "1_1") (pintype "passive"))
      (node (ref "C173") (pin "1") (pinfunction "1_1") (pintype "passive"))
      (node (ref "C174") (pin "1") (pinfunction "1_1") (pintype "passive"))
      (node (ref "C175") (pin "1") (pinfunction "1_1") (pintype "passive"))
      (node (ref "C176") (pin "1") (pinfunction "1_1") (pintype "passive"))
      (node (ref "C177") (pin "1") (pinfunction "1_1") (pintype "passive"))
      (node (ref "C178") (pin "1") (pinfunction "1_1") (pintype "passive"))
      (node (ref "C179") (pin "1") (pinfunction "1_1") (pintype "passive"))
      (node (ref "C180") (pin "1") (pinfunction "1_1") (pintype "passive"))
      (node (ref "C181") (pin "1") (pinfunction "1_1") (pintype "passive"))
      (node (ref "C182") (pin "1") (pinfunction "1_1") (pintype "passive"))
      (node (ref "C183") (pin "1") (pinfunction "1_1") (pintype "passive"))
      (node (ref "C337") (pin "2") (pinfunction "2_2") (pintype "passive"))
      (node (ref "C338") (pin "1") (pinfunction "1_1") (pintype "passive"))
      (node (ref "C339") (pin "1") (pinfunction "1_1") (pintype "passive"))
      (node (ref "C340") (pin "1") (pinfunction "1_1") (pintype "passive"))
      (node (ref "D2") (pin "2") (pinfunction "A_2") (pintype "passive"))
      (node (ref "FL1") (pin "3") (pinfunction "PSG_3") (pintype "passive"))
      (node (ref "FL1") (pin "4") (pinfunction "CG_4") (pintype "passive"))
      (node (ref "FL1") (pin "5") (pinfunction "CG_5") (pintype "passive"))
      (node (ref "FL1") (pin "6") (pinfunction "CG_6") (pintype "passive"))
      (node (ref "J7") (pin "1") (pinfunction "1_1") (pintype "passive"))
      (node (ref "J7") (pin "3") (pinfunction "3_3") (pintype "passive"))
      (node (ref "J7") (pin "S1") (pinfunction "SHIELD_S1") (pintype "passive"))
      (node (ref "J7") (pin "S2") (pinfunction "SHIELD_S2") (pintype "passive"))
      (node (ref "J7") (pin "S3") (pinfunction "SHIELD_S3") (pintype "passive"))
      (node (ref "J8") (pin "2") (pinfunction "2_2") (pintype "passive"))
      (node (ref "Q2") (pin "3") (pinfunction "S2_3") (pintype "passive"))
      (node (ref "R72") (pin "1") (pinfunction "1_1") (pintype "passive"))
      (node (ref "R76") (pin "1") (pinfunction "1_1") (pintype "passive"))
      (node (ref "R77") (pin "1") (pinfunction "1_1") (pintype "passive"))
      (node (ref "R79") (pin "2") (pinfunction "2_2") (pintype "passive"))
      (node (ref "U3") (pin "13") (pinfunction "GPO3_13") (pintype "passive"))
      (node (ref "U3") (pin "14") (pinfunction "GPO2_14") (pintype "passive"))
      (node (ref "U3") (pin "31") (pinfunction "MODE/SYNCIN_31") (pintype "passive"))
      (node (ref "U3") (pin "33") (pinfunction "GND_33") (pintype "passive"))
      (node (ref "U3") (pin "34") (pinfunction "EP_1_34") (pintype "passive"))
      (node (ref "U3") (pin "35") (pinfunction "EP_2_35") (pintype "passive"))
      (node (ref "U3") (pin "36") (pinfunction "EP_3_36") (pintype "passive"))
      (node (ref "U3") (pin "37") (pinfunction "EP_4_37") (pintype "passive"))
      (node (ref "U30") (pin "6") (pinfunction "GND_6") (pintype "passive"))
    )
    (net (code "32") (name "Net-(C183-Pad2)") (class "Default")
      (node (ref "C183") (pin "2") (pinfunction "2_2") (pintype "passive"))
      (node (ref "R78") (pin "1") (pinfunction "1_1") (pintype "passive"))
    )
    (net (code "33") (name "Net-(D19-A)") (class "Default")
      (node (ref "D19") (pin "2") (pinfunction "A_2") (pintype "passive"))
      (node (ref "R235") (pin "2") (pinfunction "2_2") (pintype "passive"))
    )
    (net (code "34") (name "Net-(L11-Pad2)") (class "Default")
      (node (ref "L11") (pin "2") (pinfunction "2_2") (pintype "passive"))
      (node (ref "R64") (pin "I1") (pinfunction "I1_I1") (pintype "passive"))
    )
    (net (code "35") (name "Net-(U3-SW1BOOT)") (class "Default")
      (node (ref "C169") (pin "1") (pinfunction "1_1") (pintype "passive"))
      (node (ref "U3") (pin "17") (pinfunction "SW1BOOT_17") (pintype "passive"))
    )
    (net (code "36") (name "Net-(U3-SW1LX_1)") (class "Default")
      (node (ref "C169") (pin "2") (pinfunction "2_2") (pintype "passive"))
      (node (ref "L12") (pin "1") (pinfunction "1_1") (pintype "passive"))
      (node (ref "U3") (pin "20") (pinfunction "SW1LX_1_20") (pintype "passive"))
      (node (ref "U3") (pin "21") (pinfunction "SW1LX_2_21") (pintype "passive"))
    )
    (net (code "37") (name "Net-(U3-SW2BO_OT)") (class "Default")
      (node (ref "C160") (pin "2") (pinfunction "2_2") (pintype "passive"))
      (node (ref "U3") (pin "12") (pinfunction "SW2BO_OT_12") (pintype "passive"))
    )
    (net (code "38") (name "Net-(U30-CT)") (class "Default")
      (node (ref "C340") (pin "2") (pinfunction "2_2") (pintype "passive"))
      (node (ref "U30") (pin "1") (pinfunction "CT_1") (pintype "passive"))
    )
    (net (code "39") (name "PMIC_VDD_DDRIO") (class "Default")
      (node (ref "R236") (pin "2") (pinfunction "2_2") (pintype "passive"))
    )
    (net (code "40") (name "unconnected-(U30-NC-Pad2)") (class "Default")
      (node (ref "U30") (pin "2") (pinfunction "NC_2") (pintype "passive+no_connect"))
    )
  )
)
